# team_flag.net
KiCad netlist of a schematic drawn in EAGLE
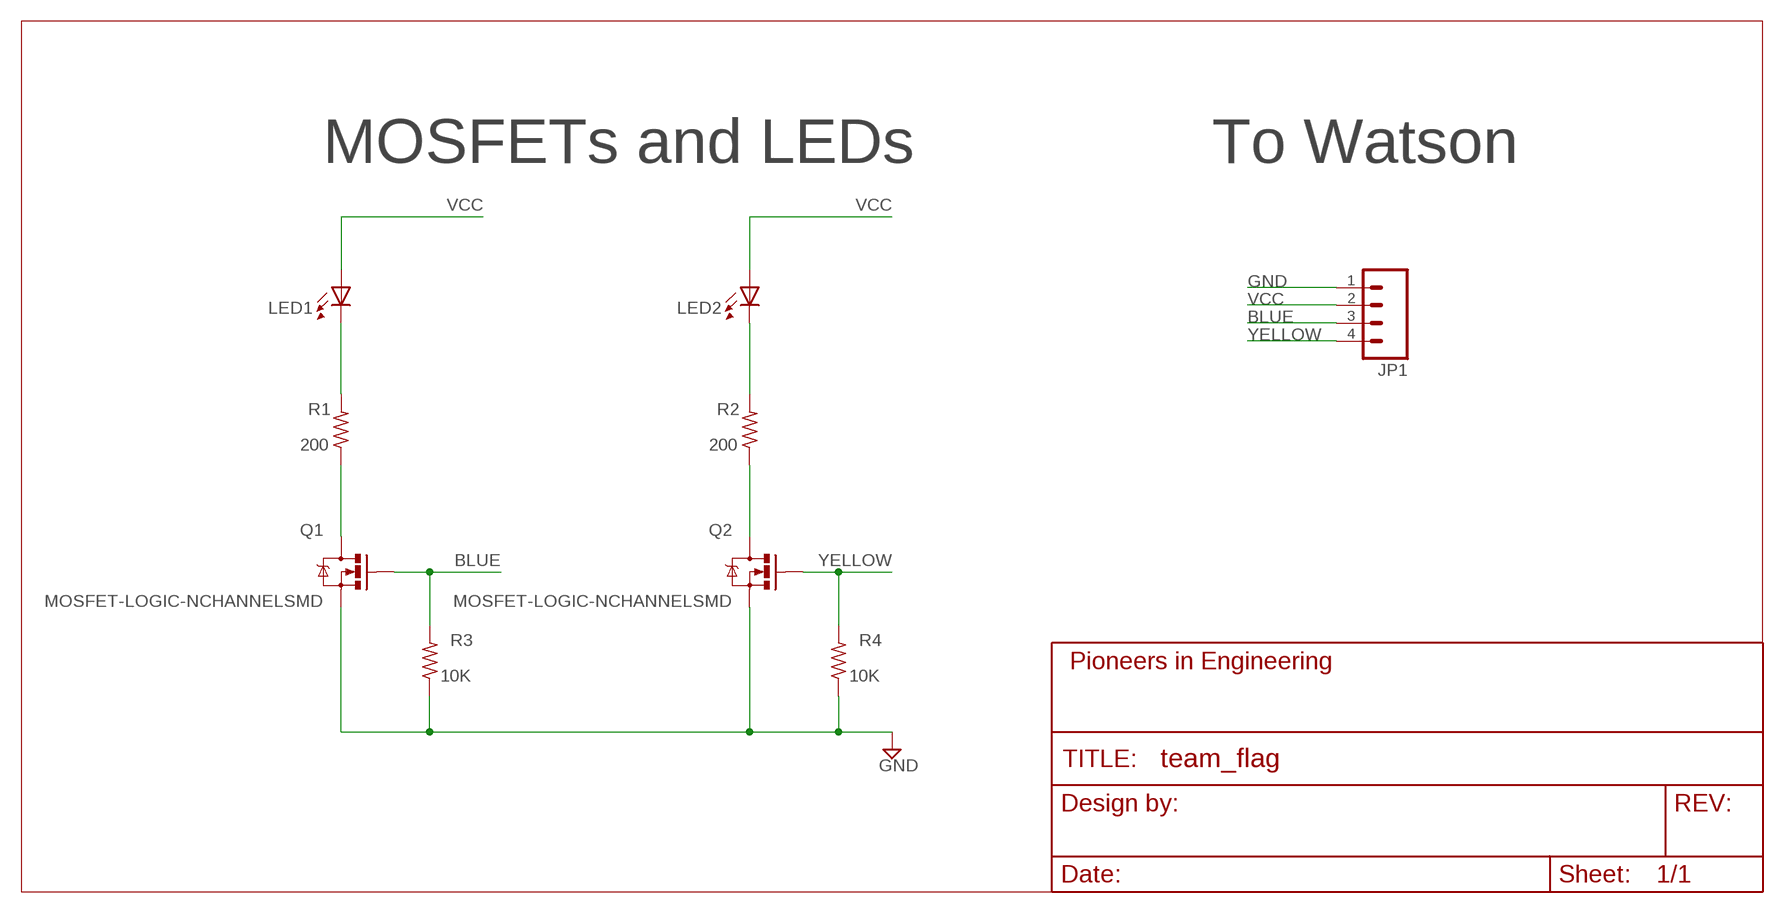
[diagram p0: schematic, sheet 1]

(export (version "E")
  (design (tool "Eeschema 10.0.6"))
  (components
    (comp (ref "JP1")
      (value "M041X04-MTA")
      (footprint "eagle-import:1X04-MTA")
      (fields (field (name "PARTNUMBER") "A1922-ND"))
      (libsource (lib "eagle-import") (part "M041X04-MTA"))
    )
    (comp (ref "LED1")
      (value "LEDLED5MM-NOFLAT")
      (footprint "eagle-import:LED5MM-NOFLAT")
      (libsource (lib "eagle-import") (part "LEDLED5MM-NOFLAT"))
    )
    (comp (ref "LED2")
      (value "LEDLED5MM-NOFLAT")
      (footprint "eagle-import:LED5MM-NOFLAT")
      (libsource (lib "eagle-import") (part "LEDLED5MM-NOFLAT"))
    )
    (comp (ref "Q1")
      (value "MOSFET-LOGIC-NCHANNELSMD")
      (footprint "eagle-import:SOT23-3-LOGIC")
      (libsource (lib "eagle-import") (part "MOSFET-LOGIC-NCHANNELSMD"))
    )
    (comp (ref "Q2")
      (value "MOSFET-LOGIC-NCHANNELSMD")
      (footprint "eagle-import:SOT23-3-LOGIC")
      (libsource (lib "eagle-import") (part "MOSFET-LOGIC-NCHANNELSMD"))
    )
    (comp (ref "R1")
      (value "200")
      (footprint "eagle-import:R0603")
      (libsource (lib "eagle-import") (part "R-US_R0603"))
    )
    (comp (ref "R2")
      (value "200")
      (footprint "eagle-import:R0603")
      (libsource (lib "eagle-import") (part "R-US_R0603"))
    )
    (comp (ref "R3")
      (value "10K")
      (footprint "eagle-import:R0603")
      (libsource (lib "eagle-import") (part "R-US_R0603"))
    )
    (comp (ref "R4")
      (value "10K")
      (footprint "eagle-import:R0603")
      (libsource (lib "eagle-import") (part "R-US_R0603"))
    )
  )
  (nets
    (net (code "1") (name "/BLUE") (class "Default")
      (node (ref "JP1") (pin "3") (pinfunction "3_3") (pintype "passive"))
      (node (ref "Q1") (pin "1") (pinfunction "G_1") (pintype "passive"))
      (node (ref "R3") (pin "2") (pinfunction "2_2") (pintype "passive"))
    )
    (net (code "2") (name "/VCC") (class "Default")
      (node (ref "JP1") (pin "2") (pinfunction "2_2") (pintype "passive"))
      (node (ref "LED1") (pin "A") (pinfunction "A_A") (pintype "passive"))
      (node (ref "LED2") (pin "A") (pinfunction "A_A") (pintype "passive"))
    )
    (net (code "3") (name "/YELLOW") (class "Default")
      (node (ref "JP1") (pin "4") (pinfunction "4_4") (pintype "passive"))
      (node (ref "Q2") (pin "1") (pinfunction "G_1") (pintype "passive"))
      (node (ref "R4") (pin "2") (pinfunction "2_2") (pintype "passive"))
    )
    (net (code "4") (name "GND") (class "Default")
      (node (ref "JP1") (pin "1") (pinfunction "1_1") (pintype "passive"))
      (node (ref "Q1") (pin "2") (pinfunction "S_2") (pintype "passive"))
      (node (ref "Q2") (pin "2") (pinfunction "S_2") (pintype "passive"))
      (node (ref "R3") (pin "1") (pinfunction "1_1") (pintype "passive"))
      (node (ref "R4") (pin "1") (pinfunction "1_1") (pintype "passive"))
    )
    (net (code "5") (name "Net-(LED1-C)") (class "Default")
      (node (ref "LED1") (pin "K") (pinfunction "C_K") (pintype "passive"))
      (node (ref "R1") (pin "2") (pinfunction "2_2") (pintype "passive"))
    )
    (net (code "6") (name "Net-(LED2-C)") (class "Default")
      (node (ref "LED2") (pin "K") (pinfunction "C_K") (pintype "passive"))
      (node (ref "R2") (pin "2") (pinfunction "2_2") (pintype "passive"))
    )
    (net (code "7") (name "Net-(Q1-D)") (class "Default")
      (node (ref "Q1") (pin "3") (pinfunction "D_3") (pintype "passive"))
      (node (ref "R1") (pin "1") (pinfunction "1_1") (pintype "passive"))
    )
    (net (code "8") (name "Net-(Q2-D)") (class "Default")
      (node (ref "Q2") (pin "3") (pinfunction "D_3") (pintype "passive"))
      (node (ref "R2") (pin "1") (pinfunction "1_1") (pintype "passive"))
    )
  )
)
